# IC_BASE.net
KiCad netlist of a schematic drawn in Altium Designer
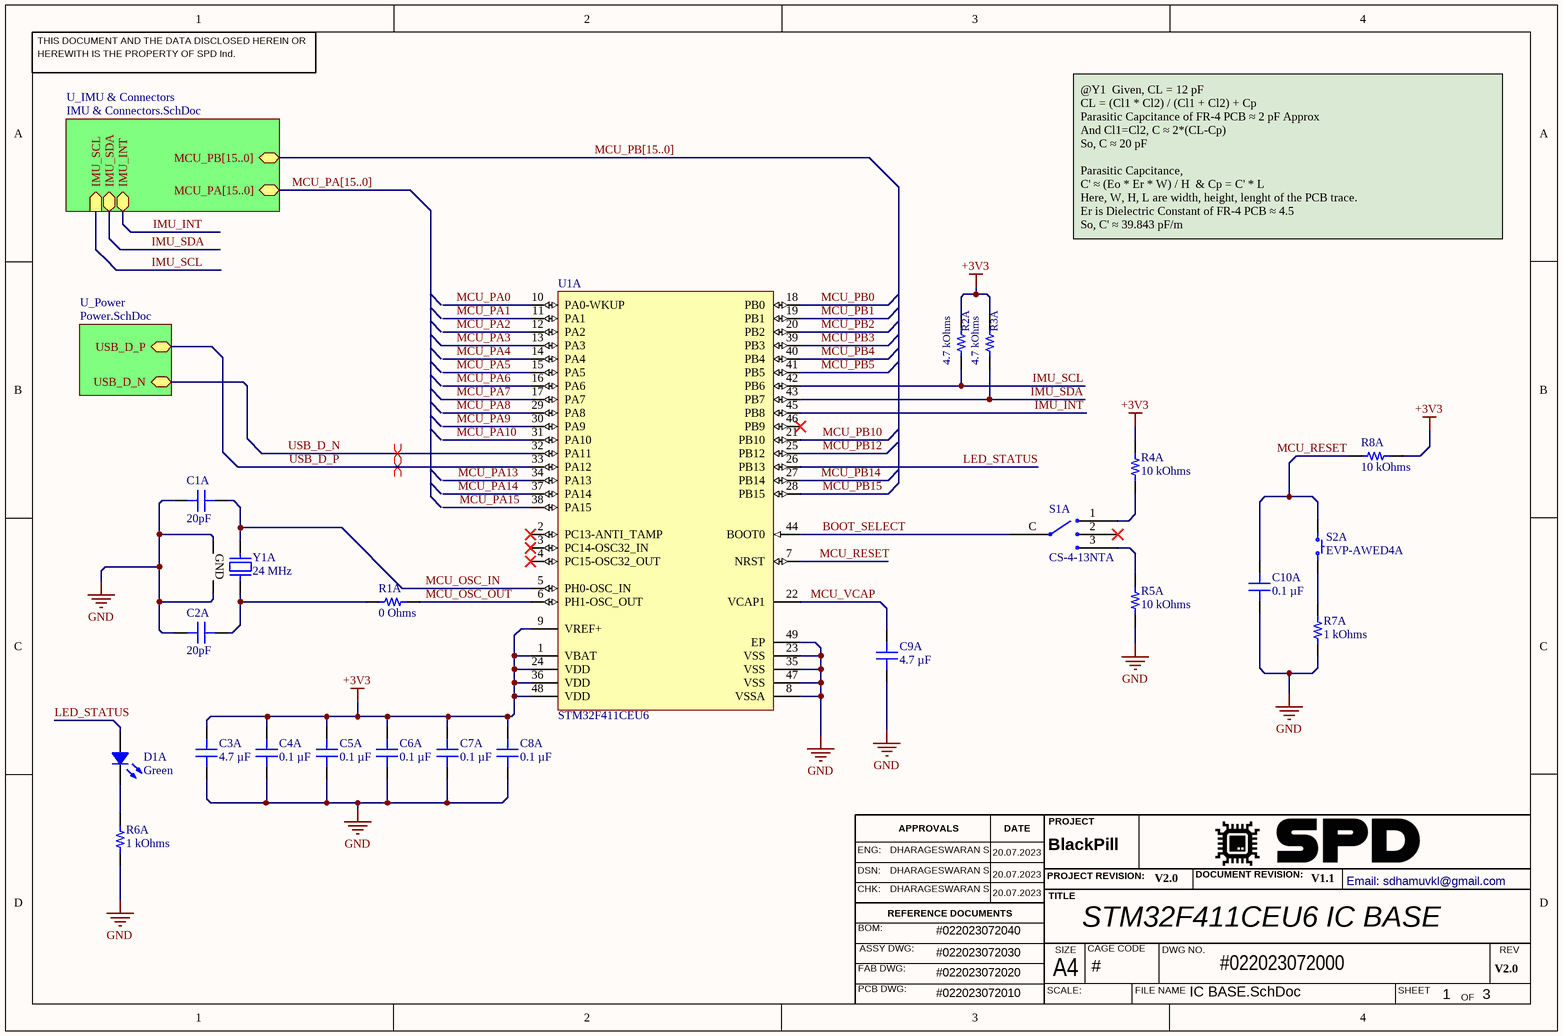
[diagram p0: IC BASE.SchDoc]

(export (version "E")
  (design (tool "Eeschema 10.0.6"))
  (components
    (comp (ref "C1A")
      (value "20pF")
      (footprint "CAP 0402_1005")
      (description "CAP CER 20PF 25V NP0 0402")
      (fields (field (name "PART NUMBER") "04023U200JAT2A") (field (name "MANUFACTURER") "AVX Corporation"))
      (libsource (lib "Postgres Altium Library - altium_library") (part "Capacitor"))
    )
    (comp (ref "C2A")
      (value "20pF")
      (footprint "CAP 0402_1005")
      (description "CAP CER 20PF 25V NP0 0402")
      (fields (field (name "PART NUMBER") "04023U200JAT2A") (field (name "MANUFACTURER") "AVX Corporation"))
      (libsource (lib "Postgres Altium Library - altium_library") (part "Capacitor"))
    )
    (comp (ref "C3A")
      (value "4.7 µF")
      (footprint "CAP 0402_1005")
      (description "CAP0402 X5R 4.7UF 10% 10V")
      (fields
        (field (name "PART NUMBER") "GMC04X5R475K10NT")
        (field (name "MANUFACTURER") "Cal-Chip Electronics, Inc.")
      )
      (libsource (lib "Postgres Altium Library - altium_library") (part "Capacitor"))
    )
    (comp (ref "C4A")
      (value "0.1 µF")
      (footprint "CAP 0402_1005")
      (description "CAP CER 100NF 10V X7R 0402")
      (fields
        (field (name "PART NUMBER") "CL05B104KP5VPNC")
        (field (name "MANUFACTURER") "Samsung Electro-Mechanics")
      )
      (libsource (lib "Postgres Altium Library - altium_library") (part "Capacitor"))
    )
    (comp (ref "C5A")
      (value "0.1 µF")
      (footprint "CAP 0402_1005")
      (description "CAP CER 100NF 10V X7R 0402")
      (fields
        (field (name "PART NUMBER") "CL05B104KP5VPNC")
        (field (name "MANUFACTURER") "Samsung Electro-Mechanics")
      )
      (libsource (lib "Postgres Altium Library - altium_library") (part "Capacitor"))
    )
    (comp (ref "C6A")
      (value "0.1 µF")
      (footprint "CAP 0402_1005")
      (description "CAP CER 100NF 10V X7R 0402")
      (fields
        (field (name "PART NUMBER") "CL05B104KP5VPNC")
        (field (name "MANUFACTURER") "Samsung Electro-Mechanics")
      )
      (libsource (lib "Postgres Altium Library - altium_library") (part "Capacitor"))
    )
    (comp (ref "C7A")
      (value "0.1 µF")
      (footprint "CAP 0402_1005")
      (description "CAP CER 100NF 10V X7R 0402")
      (fields
        (field (name "PART NUMBER") "CL05B104KP5VPNC")
        (field (name "MANUFACTURER") "Samsung Electro-Mechanics")
      )
      (libsource (lib "Postgres Altium Library - altium_library") (part "Capacitor"))
    )
    (comp (ref "C8A")
      (value "0.1 µF")
      (footprint "CAP 0402_1005")
      (description "CAP CER 100NF 10V X7R 0402")
      (fields
        (field (name "PART NUMBER") "CL05B104KP5VPNC")
        (field (name "MANUFACTURER") "Samsung Electro-Mechanics")
      )
      (libsource (lib "Postgres Altium Library - altium_library") (part "Capacitor"))
    )
    (comp (ref "C9A")
      (value "4.7 µF")
      (footprint "CAP 0402_1005")
      (description "CAP0402 X5R 4.7UF 10% 10V")
      (fields
        (field (name "PART NUMBER") "GMC04X5R475K10NT")
        (field (name "MANUFACTURER") "Cal-Chip Electronics, Inc.")
      )
      (libsource (lib "Postgres Altium Library - altium_library") (part "Capacitor"))
    )
    (comp (ref "C10A")
      (value "0.1 µF")
      (footprint "CAP 0402_1005")
      (description "CAP CER 100NF 10V X7R 0402")
      (fields
        (field (name "PART NUMBER") "CL05B104KP5VPNC")
        (field (name "MANUFACTURER") "Samsung Electro-Mechanics")
      )
      (libsource (lib "Postgres Altium Library - altium_library") (part "Capacitor"))
    )
    (comp (ref "D1A")
      (value "Green")
      (footprint "LED 0402_1005 GREEN")
      (description "LED GREEN DIFFUSED 0402 SMD")
      (fields (field (name "PART NUMBER") "HSMG-C280") (field (name "MANUFACTURER") "Broadcom Limited"))
      (libsource (lib "Postgres Altium Library - altium_library") (part "LED"))
    )
    (comp (ref "R1A")
      (value "0 Ohms")
      (footprint "RES 0402_1005")
      (description "RES SMD 0 OHM JUMPER 1/16W 0402")
      (fields (field (name "PART NUMBER") "AC0402JR-070RL") (field (name "TOLERANCE") "Jumper"))
      (libsource (lib "Postgres Altium Library - altium_library") (part "Resistor"))
    )
    (comp (ref "R2A")
      (value "4.7 kOhms")
      (footprint "RES 0402_1005")
      (description "RES SMD 4.7K OHM 1% 1/16W 0402")
      (fields (field (name "PART NUMBER") "AC0402FR-074K7L") (field (name "TOLERANCE") "±1%"))
      (libsource (lib "Postgres Altium Library - altium_library") (part "Resistor"))
    )
    (comp (ref "R3A")
      (value "4.7 kOhms")
      (footprint "RES 0402_1005")
      (description "RES SMD 4.7K OHM 1% 1/16W 0402")
      (fields (field (name "PART NUMBER") "AC0402FR-074K7L") (field (name "TOLERANCE") "±1%"))
      (libsource (lib "Postgres Altium Library - altium_library") (part "Resistor"))
    )
    (comp (ref "R4A")
      (value "10 kOhms")
      (footprint "RES 0402_1005")
      (description "RES SMD 10K OHM 1% 1/16W 0402")
      (fields (field (name "PART NUMBER") "AA0402FR-0710KL") (field (name "TOLERANCE") "±1%"))
      (libsource (lib "Postgres Altium Library - altium_library") (part "Resistor"))
    )
    (comp (ref "R5A")
      (value "10 kOhms")
      (footprint "RES 0402_1005")
      (description "RES SMD 10K OHM 1% 1/16W 0402")
      (fields (field (name "PART NUMBER") "AA0402FR-0710KL") (field (name "TOLERANCE") "±1%"))
      (libsource (lib "Postgres Altium Library - altium_library") (part "Resistor"))
    )
    (comp (ref "R6A")
      (value "1 kOhms")
      (footprint "RES 0402_1005")
      (description "RES SMD 1K OHM 1% 1/16W 0402")
      (fields (field (name "PART NUMBER") "AA0402FR-071KL") (field (name "TOLERANCE") "±1%"))
      (libsource (lib "Postgres Altium Library - altium_library") (part "Resistor"))
    )
    (comp (ref "R7A")
      (value "1 kOhms")
      (footprint "RES 0402_1005")
      (description "RES SMD 1K OHM 1% 1/16W 0402")
      (fields (field (name "PART NUMBER") "AA0402FR-071KL") (field (name "TOLERANCE") "±1%"))
      (libsource (lib "Postgres Altium Library - altium_library") (part "Resistor"))
    )
    (comp (ref "R8A")
      (value "10 kOhms")
      (footprint "RES 0402_1005")
      (description "RES SMD 10K OHM 1% 1/16W 0402")
      (fields (field (name "PART NUMBER") "AA0402FR-0710KL") (field (name "TOLERANCE") "±1%"))
      (libsource (lib "Postgres Altium Library - altium_library") (part "Resistor"))
    )
    (comp (ref "S1A")
      (value "CS-4-13NTA")
      (footprint "NIDEC COPAL CS-4-13NTA")
      (description "SWITCH ROTARY DIP SP3T 100MA 16V")
      (fields (field (name "MANUFACTURER") "Nidec Copal Electronics"))
      (libsource (lib "Postgres Altium Library - altium_library") (part "NIDEC COPAL CS-4-13NTA"))
    )
    (comp (ref "S2A")
      (value "EVP-AWED4A")
      (footprint "PANASONIC EVPAW")
      (description "3.0MM X 2.0MM / 3.3N / 0.15MM ST")
      (fields (field (name "MANUFACTURER") "Panasonic Electronic Components"))
      (libsource (lib "Postgres Altium Library - altium_library") (part "SPST-NO 2 PIN"))
    )
    (comp (ref "U1A")
      (value "STM32F411CEU6")
      (footprint "STM-UFQFPN48_L")
      (libsource (lib "Altium Content Vault") (part "MC-ARM-STM32F411-UFQFPN48"))
    )
    (comp (ref "Y1A")
      (value "24 MHz")
      (footprint "EPSON TSX-3225")
      (description "CRYSTAL 24.0000MHZ 9PF SMD")
      (fields (field (name "PART NUMBER") "TSX-3225 24.0000MF15X-AC3") (field (name "MANUFACTURER") "EPSON"))
      (libsource (lib "Postgres Altium Library - altium_library") (part "Epson Crystal TSX-3225"))
    )
  )
  (nets
    (net (code "9") (name "+3V3") (class "Default")
      (node (ref "C3A") (pin "2") (pinfunction "2_2") (pintype "passive"))
      (node (ref "C4A") (pin "2") (pinfunction "2_2") (pintype "passive"))
      (node (ref "C5A") (pin "2") (pinfunction "2_2") (pintype "passive"))
      (node (ref "C6A") (pin "2") (pinfunction "2_2") (pintype "passive"))
      (node (ref "C7A") (pin "2") (pinfunction "2_2") (pintype "passive"))
      (node (ref "C8A") (pin "2") (pinfunction "2_2") (pintype "passive"))
      (node (ref "R2A") (pin "2") (pinfunction "2_2") (pintype "passive"))
      (node (ref "R3A") (pin "2") (pinfunction "2_2") (pintype "passive"))
      (node (ref "R4A") (pin "2") (pinfunction "2_2") (pintype "passive"))
      (node (ref "R8A") (pin "1") (pinfunction "1_1") (pintype "passive"))
      (node (ref "U1A") (pin "1") (pinfunction "VBAT_1") (pintype "power_in"))
      (node (ref "U1A") (pin "24") (pinfunction "VDD_24") (pintype "power_in"))
      (node (ref "U1A") (pin "36") (pinfunction "VDD_36") (pintype "power_in"))
      (node (ref "U1A") (pin "48") (pinfunction "VDD_48") (pintype "power_in"))
      (node (ref "U1A") (pin "9") (pinfunction "VREF+_9") (pintype "power_in"))
    )
    (net (code "10") (name "/BOOT_SELECT") (class "Default")
      (node (ref "S1A") (pin "C") (pinfunction "C_C") (pintype "passive"))
      (node (ref "U1A") (pin "44") (pinfunction "BOOT0_44") (pintype "input"))
    )
    (net (code "11") (name "/IMU_INT") (class "Default")
      (node (ref "U1A") (pin "45") (pinfunction "PB8_45") (pintype "bidirectional"))
    )
    (net (code "12") (name "/IMU_SCL") (class "Default")
      (node (ref "R2A") (pin "1") (pinfunction "1_1") (pintype "passive"))
      (node (ref "U1A") (pin "42") (pinfunction "PB6_42") (pintype "bidirectional"))
    )
    (net (code "13") (name "/IMU_SDA") (class "Default")
      (node (ref "R3A") (pin "1") (pinfunction "1_1") (pintype "passive"))
      (node (ref "U1A") (pin "43") (pinfunction "PB7_43") (pintype "bidirectional"))
    )
    (net (code "14") (name "/LED_STATUS") (class "Default")
      (node (ref "D1A") (pin "1") (pinfunction "1_1") (pintype "passive"))
      (node (ref "U1A") (pin "26") (pinfunction "PB13_26") (pintype "bidirectional"))
    )
    (net (code "15") (name "/MCU_OSC_IN") (class "Default")
      (node (ref "C1A") (pin "2") (pinfunction "2_2") (pintype "passive"))
      (node (ref "U1A") (pin "5") (pinfunction "PH0-OSC_IN_5") (pintype "bidirectional"))
      (node (ref "Y1A") (pin "1") (pinfunction "1_1") (pintype "passive"))
    )
    (net (code "16") (name "/MCU_OSC_OUT") (class "Default")
      (node (ref "R1A") (pin "2") (pinfunction "2_2") (pintype "passive"))
      (node (ref "U1A") (pin "6") (pinfunction "PH1-OSC_OUT_6") (pintype "bidirectional"))
    )
    (net (code "17") (name "/MCU_PA0") (class "Default")
      (node (ref "U1A") (pin "10") (pinfunction "PA0-WKUP_10") (pintype "bidirectional"))
    )
    (net (code "18") (name "/MCU_PA1") (class "Default")
      (node (ref "U1A") (pin "11") (pinfunction "PA1_11") (pintype "bidirectional"))
    )
    (net (code "19") (name "/MCU_PA2") (class "Default")
      (node (ref "U1A") (pin "12") (pinfunction "PA2_12") (pintype "bidirectional"))
    )
    (net (code "20") (name "/MCU_PA3") (class "Default")
      (node (ref "U1A") (pin "13") (pinfunction "PA3_13") (pintype "bidirectional"))
    )
    (net (code "21") (name "/MCU_PA4") (class "Default")
      (node (ref "U1A") (pin "14") (pinfunction "PA4_14") (pintype "bidirectional"))
    )
    (net (code "22") (name "/MCU_PA5") (class "Default")
      (node (ref "U1A") (pin "15") (pinfunction "PA5_15") (pintype "bidirectional"))
    )
    (net (code "23") (name "/MCU_PA6") (class "Default")
      (node (ref "U1A") (pin "16") (pinfunction "PA6_16") (pintype "bidirectional"))
    )
    (net (code "24") (name "/MCU_PA7") (class "Default")
      (node (ref "U1A") (pin "17") (pinfunction "PA7_17") (pintype "bidirectional"))
    )
    (net (code "25") (name "/MCU_PA8") (class "Default")
      (node (ref "U1A") (pin "29") (pinfunction "PA8_29") (pintype "bidirectional"))
    )
    (net (code "26") (name "/MCU_PA9") (class "Default")
      (node (ref "U1A") (pin "30") (pinfunction "PA9_30") (pintype "bidirectional"))
    )
    (net (code "27") (name "/MCU_PA10") (class "Default")
      (node (ref "U1A") (pin "31") (pinfunction "PA10_31") (pintype "bidirectional"))
    )
    (net (code "28") (name "/MCU_PA13") (class "Default")
      (node (ref "U1A") (pin "34") (pinfunction "PA13_34") (pintype "bidirectional"))
    )
    (net (code "29") (name "/MCU_PA14") (class "Default")
      (node (ref "U1A") (pin "37") (pinfunction "PA14_37") (pintype "bidirectional"))
    )
    (net (code "30") (name "/MCU_PA15") (class "Default")
      (node (ref "U1A") (pin "38") (pinfunction "PA15_38") (pintype "bidirectional"))
    )
    (net (code "32") (name "/MCU_PB0") (class "Default")
      (node (ref "U1A") (pin "18") (pinfunction "PB0_18") (pintype "bidirectional"))
    )
    (net (code "33") (name "/MCU_PB1") (class "Default")
      (node (ref "U1A") (pin "19") (pinfunction "PB1_19") (pintype "bidirectional"))
    )
    (net (code "34") (name "/MCU_PB2") (class "Default")
      (node (ref "U1A") (pin "20") (pinfunction "PB2_20") (pintype "bidirectional"))
    )
    (net (code "35") (name "/MCU_PB3") (class "Default")
      (node (ref "U1A") (pin "39") (pinfunction "PB3_39") (pintype "bidirectional"))
    )
    (net (code "36") (name "/MCU_PB4") (class "Default")
      (node (ref "U1A") (pin "40") (pinfunction "PB4_40") (pintype "bidirectional"))
    )
    (net (code "37") (name "/MCU_PB5") (class "Default")
      (node (ref "U1A") (pin "41") (pinfunction "PB5_41") (pintype "bidirectional"))
    )
    (net (code "38") (name "/MCU_PB10") (class "Default")
      (node (ref "U1A") (pin "21") (pinfunction "PB10_21") (pintype "bidirectional"))
    )
    (net (code "39") (name "/MCU_PB12") (class "Default")
      (node (ref "U1A") (pin "25") (pinfunction "PB12_25") (pintype "bidirectional"))
    )
    (net (code "40") (name "/MCU_PB14") (class "Default")
      (node (ref "U1A") (pin "27") (pinfunction "PB14_27") (pintype "bidirectional"))
    )
    (net (code "41") (name "/MCU_PB15") (class "Default")
      (node (ref "U1A") (pin "28") (pinfunction "PB15_28") (pintype "bidirectional"))
    )
    (net (code "43") (name "/MCU_RESET") (class "Default")
      (node (ref "C10A") (pin "2") (pinfunction "2_2") (pintype "passive"))
      (node (ref "R8A") (pin "2") (pinfunction "2_2") (pintype "passive"))
      (node (ref "S2A") (pin "1") (pinfunction "1_1") (pintype "passive"))
      (node (ref "U1A") (pin "7") (pinfunction "NRST_7") (pintype "bidirectional"))
    )
    (net (code "44") (name "/MCU_VCAP") (class "Default")
      (node (ref "C9A") (pin "2") (pinfunction "2_2") (pintype "passive"))
      (node (ref "U1A") (pin "22") (pinfunction "VCAP1_22") (pintype "passive"))
    )
    (net (code "45") (name "/USB_D_N") (class "Default")
      (node (ref "U1A") (pin "32") (pinfunction "PA11_32") (pintype "bidirectional"))
    )
    (net (code "46") (name "/USB_D_P") (class "Default")
      (node (ref "U1A") (pin "33") (pinfunction "PA12_33") (pintype "bidirectional"))
    )
    (net (code "47") (name "GND") (class "Default")
      (node (ref "C10A") (pin "1") (pinfunction "1_1") (pintype "passive"))
      (node (ref "C1A") (pin "1") (pinfunction "1_1") (pintype "passive"))
      (node (ref "C2A") (pin "1") (pinfunction "1_1") (pintype "passive"))
      (node (ref "C3A") (pin "1") (pinfunction "1_1") (pintype "passive"))
      (node (ref "C4A") (pin "1") (pinfunction "1_1") (pintype "passive"))
      (node (ref "C5A") (pin "1") (pinfunction "1_1") (pintype "passive"))
      (node (ref "C6A") (pin "1") (pinfunction "1_1") (pintype "passive"))
      (node (ref "C7A") (pin "1") (pinfunction "1_1") (pintype "passive"))
      (node (ref "C8A") (pin "1") (pinfunction "1_1") (pintype "passive"))
      (node (ref "C9A") (pin "1") (pinfunction "1_1") (pintype "passive"))
      (node (ref "R5A") (pin "1") (pinfunction "1_1") (pintype "passive"))
      (node (ref "R6A") (pin "1") (pinfunction "1_1") (pintype "passive"))
      (node (ref "R7A") (pin "1") (pinfunction "1_1") (pintype "passive"))
      (node (ref "U1A") (pin "23") (pinfunction "VSS_23") (pintype "power_in"))
      (node (ref "U1A") (pin "35") (pinfunction "VSS_35") (pintype "power_in"))
      (node (ref "U1A") (pin "47") (pinfunction "VSS_47") (pintype "power_in"))
      (node (ref "U1A") (pin "49") (pinfunction "EP_49") (pintype "power_in"))
      (node (ref "U1A") (pin "8") (pinfunction "VSSA_8") (pintype "power_in"))
      (node (ref "Y1A") (pin "2") (pinfunction "GND_2") (pintype "passive"))
      (node (ref "Y1A") (pin "4") (pinfunction "GND_4") (pintype "passive"))
    )
    (net (code "48") (name "Net-(C2A-Pad2)") (class "Default")
      (node (ref "C2A") (pin "2") (pinfunction "2_2") (pintype "passive"))
      (node (ref "R1A") (pin "1") (pinfunction "1_1") (pintype "passive"))
      (node (ref "Y1A") (pin "3") (pinfunction "3_3") (pintype "passive"))
    )
    (net (code "49") (name "Net-(D1A-Pad2)") (class "Default")
      (node (ref "D1A") (pin "2") (pinfunction "2_2") (pintype "passive"))
      (node (ref "R6A") (pin "2") (pinfunction "2_2") (pintype "passive"))
    )
    (net (code "50") (name "Net-(R4A-Pad1)") (class "Default")
      (node (ref "R4A") (pin "1") (pinfunction "1_1") (pintype "passive"))
      (node (ref "S1A") (pin "1") (pinfunction "1_1") (pintype "passive"))
    )
    (net (code "51") (name "Net-(R5A-Pad2)") (class "Default")
      (node (ref "R5A") (pin "2") (pinfunction "2_2") (pintype "passive"))
      (node (ref "S1A") (pin "3") (pinfunction "3_3") (pintype "passive"))
    )
    (net (code "52") (name "Net-(R7A-Pad2)") (class "Default")
      (node (ref "R7A") (pin "2") (pinfunction "2_2") (pintype "passive"))
      (node (ref "S2A") (pin "2") (pinfunction "2_2") (pintype "passive"))
    )
    (net (code "53") (name "unconnected-(S1A-Pad2)") (class "Default")
      (node (ref "S1A") (pin "2") (pinfunction "2_2") (pintype "passive+no_connect"))
    )
    (net (code "54") (name "unconnected-(U1A-PB9-Pad46)") (class "Default")
      (node (ref "U1A") (pin "46") (pinfunction "PB9_46") (pintype "bidirectional+no_connect"))
    )
    (net (code "55") (name "unconnected-(U1A-PC13-ANTI_TAMP-Pad2)") (class "Default")
      (node (ref "U1A") (pin "2") (pinfunction "PC13-ANTI_TAMP_2") (pintype "bidirectional+no_connect"))
    )
    (net (code "56") (name "unconnected-(U1A-PC14-OSC32_IN-Pad3)") (class "Default")
      (node (ref "U1A") (pin "3") (pinfunction "PC14-OSC32_IN_3") (pintype "bidirectional+no_connect"))
    )
    (net (code "57") (name "unconnected-(U1A-PC15-OSC32_OUT-Pad4)") (class "Default")
      (node (ref "U1A") (pin "4") (pinfunction "PC15-OSC32_OUT_4") (pintype "bidirectional+no_connect"))
    )
  )
)
